# P-MT3620RDB-1-7_WiFi.net
KiCad netlist of a schematic drawn in Altium Designer
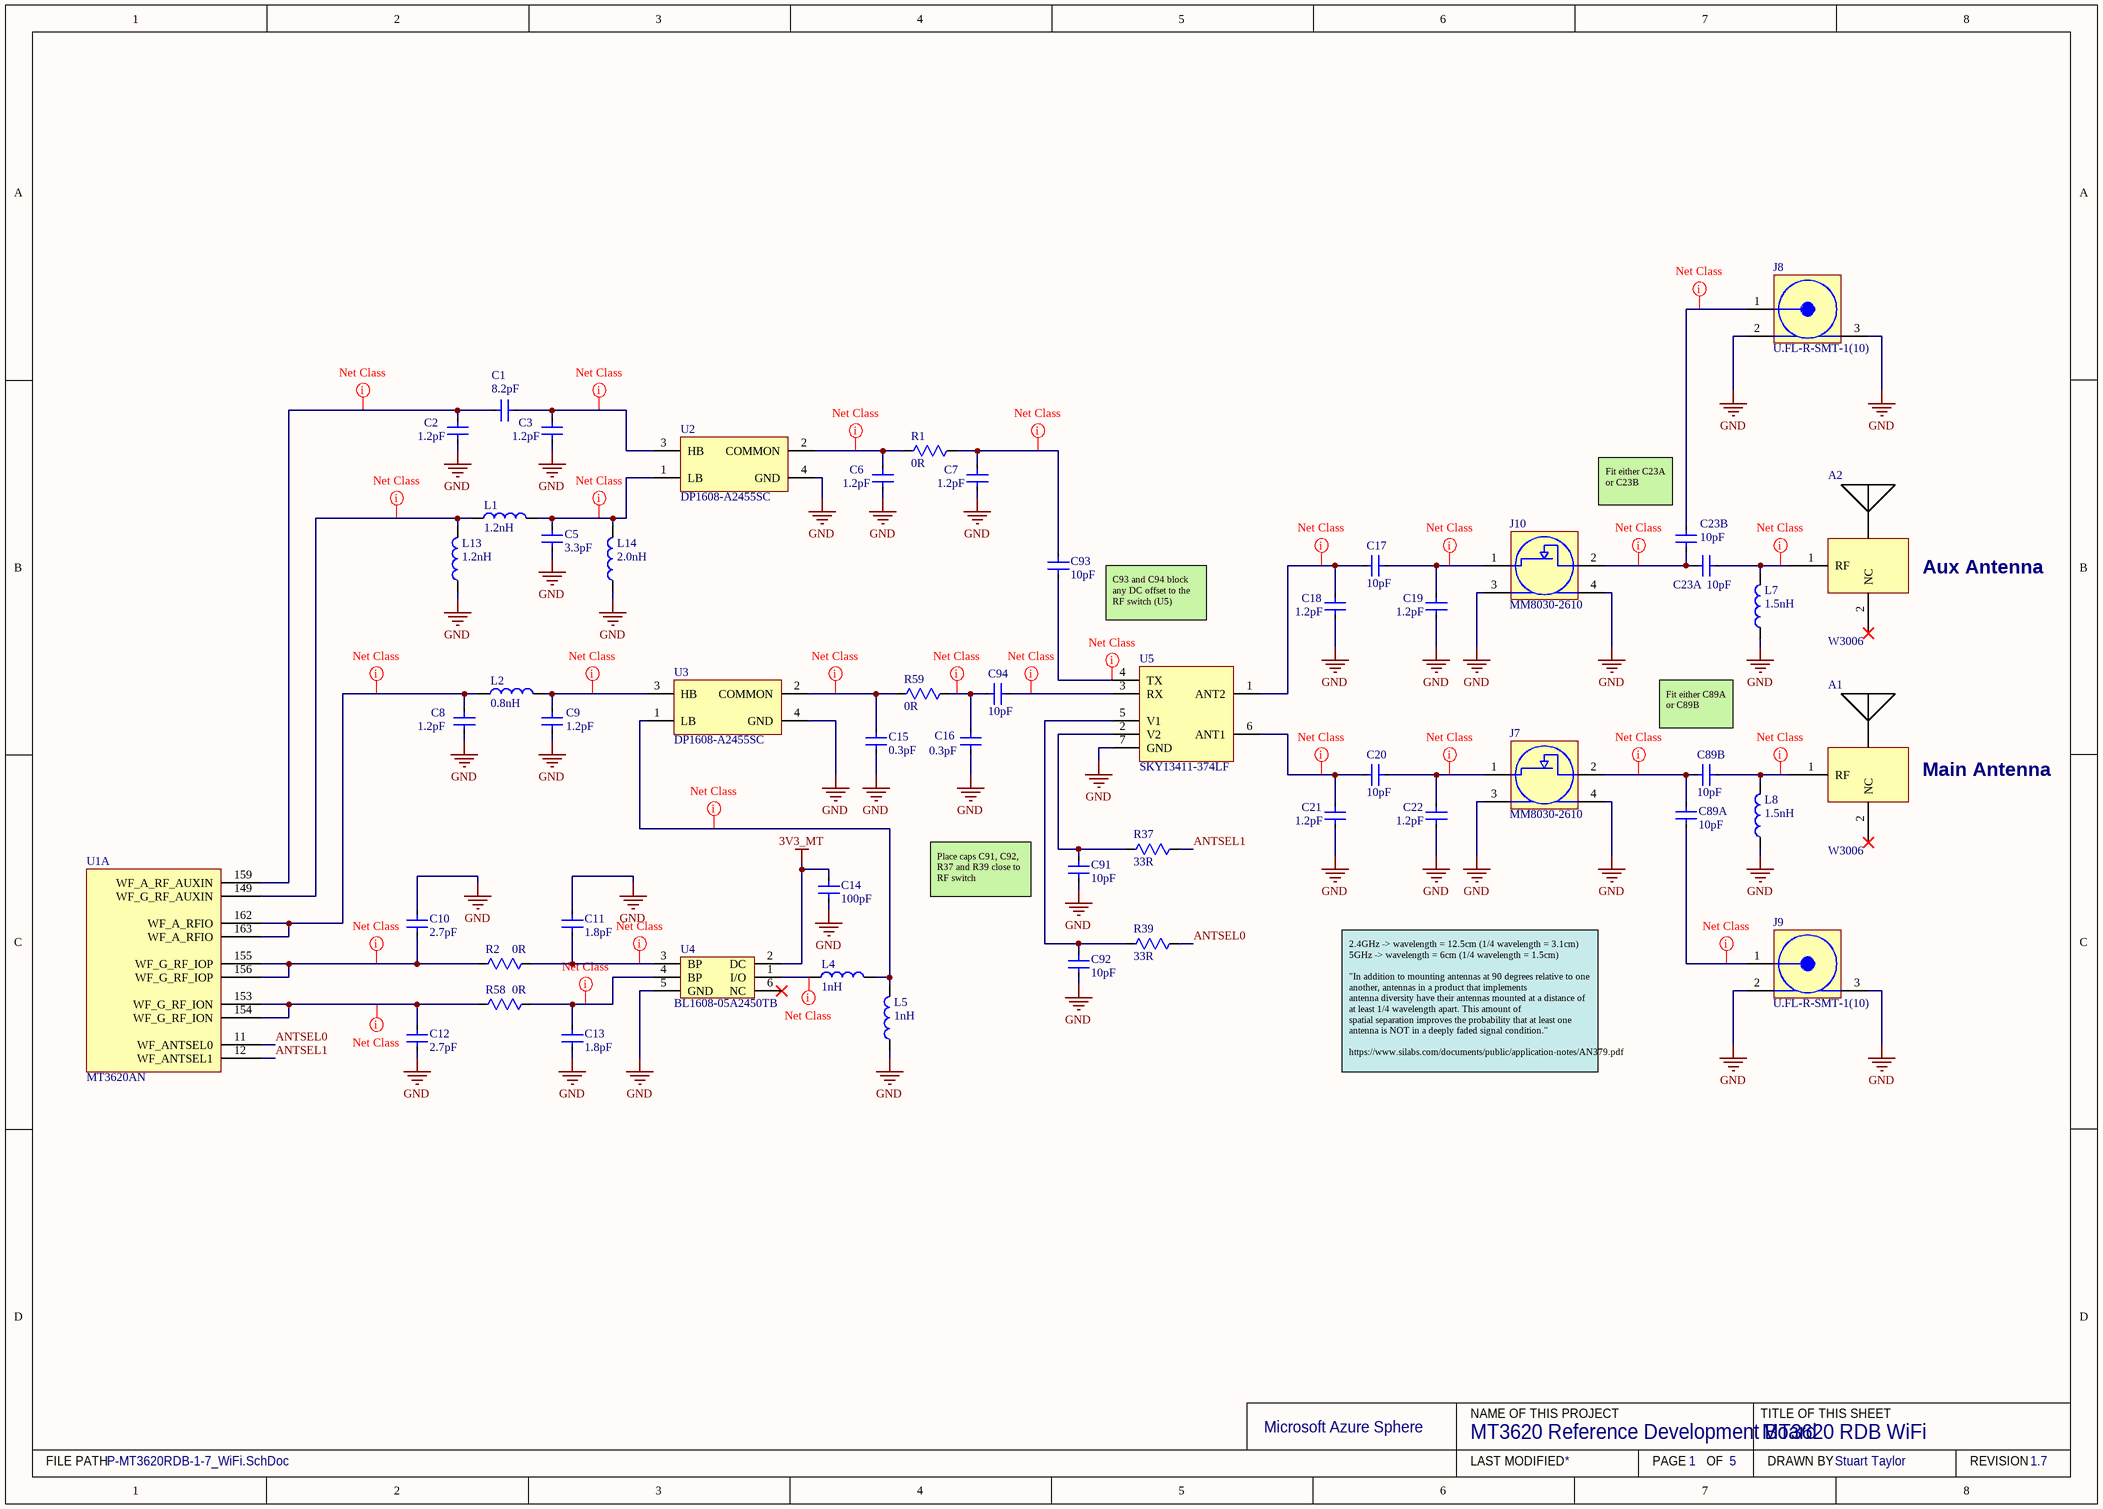
[diagram p0: P-MT3620RDB-1-7_WiFi.SchDoc]

(export (version "E")
  (design (tool "Eeschema 10.0.6"))
  (components
    (comp (ref "A1")
      (value "W3006")
      (footprint "W3006")
      (description "W3006 Chip Antenna")
      (fields (field (name "MANUFACTURER") "Pulse Electronics Corporation"))
      (libsource (lib "Pulse_W3006") (part "W3006"))
    )
    (comp (ref "A2")
      (value "W3006")
      (footprint "W3006")
      (description "W3006 Chip Antenna")
      (fields (field (name "MANUFACTURER") "Pulse Electronics Corporation"))
      (libsource (lib "Pulse_W3006") (part "W3006"))
    )
    (comp (ref "C1")
      (value "8.2pF")
      (footprint "TDK 2010")
      (description "CAP CER 8.2PF 25V NP0 0201")
      (fields
        (field (name "MANUFACTURER") "Murata")
        (field (name "MANUFACTURER PART NUMBER") "GJM0335C1E8R2CB01D")
      )
      (libsource (lib "Murata") (part "GJM0335C1E8R2CB01D"))
    )
    (comp (ref "C2")
      (value "1.2pF")
      (footprint "TDK 2010")
      (description "CAP CER 1.2PF 25V C0G 0201")
      (fields
        (field (name "MANUFACTURER") "TDK Corporation")
        (field (name "MANUFACTURER PART NUMBER") "C0603C0G1E1R2B")
      )
      (libsource (lib "TDK_Capacitor_C_0201") (part "1.2pF 0201 25V"))
    )
    (comp (ref "C3")
      (value "1.2pF")
      (footprint "TDK 2010")
      (description "CAP CER 1.2PF 25V C0G 0201")
      (fields
        (field (name "MANUFACTURER") "TDK Corporation")
        (field (name "MANUFACTURER PART NUMBER") "C0603C0G1E1R2B")
      )
      (libsource (lib "TDK_Capacitor_C_0201") (part "1.2pF 0201 25V"))
    )
    (comp (ref "C5")
      (value "3.3pF")
      (footprint "TDK 2010")
      (description "Cap Ceramic 3.3pF 25V C0G 0.25pF SMD 0201 125C T/R")
      (fields
        (field (name "MANUFACTURER") "TDK")
        (field (name "MANUFACTURER PART NUMBER") "CGA1A2C0G1E3R3C030BA")
      )
      (libsource (lib "TDK_Capacitor_C_0201") (part "3.3pF 0201 25V"))
    )
    (comp (ref "C6")
      (value "1.2pF")
      (footprint "TDK 2010")
      (description "CAP CER 1.2PF 25V C0G 0201")
      (fields
        (field (name "MANUFACTURER") "TDK Corporation")
        (field (name "MANUFACTURER PART NUMBER") "C0603C0G1E1R2B")
      )
      (libsource (lib "TDK_Capacitor_C_0201") (part "1.2pF 0201 25V"))
    )
    (comp (ref "C7")
      (value "1.2pF")
      (footprint "TDK 2010")
      (description "CAP CER 1.2PF 25V C0G 0201")
      (fields
        (field (name "MANUFACTURER") "TDK Corporation")
        (field (name "MANUFACTURER PART NUMBER") "C0603C0G1E1R2B")
      )
      (libsource (lib "TDK_Capacitor_C_0201") (part "1.2pF 0201 25V"))
    )
    (comp (ref "C8")
      (value "1.2pF")
      (footprint "TDK 2010")
      (description "CAP CER 1.2PF 25V C0G 0201")
      (fields
        (field (name "MANUFACTURER") "TDK Corporation")
        (field (name "MANUFACTURER PART NUMBER") "C0603C0G1E1R2B")
      )
      (libsource (lib "TDK_Capacitor_C_0201") (part "1.2pF 0201 25V"))
    )
    (comp (ref "C9")
      (value "1.2pF")
      (footprint "TDK 2010")
      (description "CAP CER 1.2PF 25V C0G 0201")
      (fields
        (field (name "MANUFACTURER") "TDK Corporation")
        (field (name "MANUFACTURER PART NUMBER") "C0603C0G1E1R2B")
      )
      (libsource (lib "TDK_Capacitor_C_0201") (part "1.2pF 0201 25V"))
    )
    (comp (ref "C10")
      (value "2.7pF")
      (footprint "TDK 2010")
      (description "CAP CER 2.7PF 25V C0G 0201")
      (fields (field (name "MANUFACTURER") "TDK") (field (name "MANUFACTURER PART NUMBER") "C0603C0G1E2R7B"))
      (libsource (lib "TDK_Capacitor_C_0201") (part "2.7pF 0201 25V"))
    )
    (comp (ref "C11")
      (value "1.8pF")
      (footprint "TDK 2010")
      (description "CAP CER 1.8PF 25V NP0 0201")
      (fields
        (field (name "MANUFACTURER") "Murata")
        (field (name "MANUFACTURER PART NUMBER") "GJM0335C1E1R8CB01D")
      )
      (libsource (lib "Murata") (part "GJM0335C1E1R8CB01D"))
    )
    (comp (ref "C12")
      (value "2.7pF")
      (footprint "TDK 2010")
      (description "CAP CER 2.7PF 25V C0G 0201")
      (fields (field (name "MANUFACTURER") "TDK") (field (name "MANUFACTURER PART NUMBER") "C0603C0G1E2R7B"))
      (libsource (lib "TDK_Capacitor_C_0201") (part "2.7pF 0201 25V"))
    )
    (comp (ref "C13")
      (value "1.8pF")
      (footprint "TDK 2010")
      (description "CAP CER 1.8PF 25V NP0 0201")
      (fields
        (field (name "MANUFACTURER") "Murata")
        (field (name "MANUFACTURER PART NUMBER") "GJM0335C1E1R8CB01D")
      )
      (libsource (lib "Murata") (part "GJM0335C1E1R8CB01D"))
    )
    (comp (ref "C14")
      (value "100pF")
      (footprint "CAPC1005-EIA0402 0.55MM MED")
      (description "CAP CER 100PF 50V 5% NP0 0402")
      (fields
        (field (name "MANUFACTURER") "TDK Corporation")
        (field (name "MANUFACTURER PART NUMBER") "C1005C0G1H101J050BA")
        (field (name "CAPACITANCE") "100pF")
      )
      (libsource (lib "TDK_Capacitor_C_0402") (part "100pF 0402 C0G, NP0 50V"))
    )
    (comp (ref "C15")
      (value "0.3pF")
      (footprint "TDK 2010")
      (description "CAP CER 0.3PF 25V C0G 0201")
      (fields
        (field (name "MANUFACTURER") "TDK Corporation")
        (field (name "MANUFACTURER PART NUMBER") "C0603C0G1E0R3B")
      )
      (libsource (lib "TDK_Capacitor_C_0201") (part "0.3pF 0201 25V"))
    )
    (comp (ref "C16")
      (value "0.3pF")
      (footprint "TDK 2010")
      (description "CAP CER 0.3PF 25V C0G 0201")
      (fields
        (field (name "MANUFACTURER") "TDK Corporation")
        (field (name "MANUFACTURER PART NUMBER") "C0603C0G1E0R3B")
      )
      (libsource (lib "TDK_Capacitor_C_0201") (part "0.3pF 0201 25V"))
    )
    (comp (ref "C17")
      (value "10pF")
      (footprint "TDK 2010")
      (description "CAP CER 10PF 25V C0G 0201")
      (fields
        (field (name "MANUFACTURER") "TDK Corporation")
        (field (name "MANUFACTURER PART NUMBER") "C0603C0G1E100D030BA")
      )
      (libsource (lib "TDK_Capacitor_C_0201") (part "10pF 0201 25V"))
    )
    (comp (ref "C18")
      (value "1.2pF")
      (footprint "TDK 2010")
      (description "CAP CER 1.2PF 25V C0G 0201")
      (fields
        (field (name "MANUFACTURER") "TDK Corporation")
        (field (name "MANUFACTURER PART NUMBER") "C0603C0G1E1R2B")
      )
      (libsource (lib "TDK_Capacitor_C_0201") (part "1.2pF 0201 25V"))
    )
    (comp (ref "C19")
      (value "1.2pF")
      (footprint "TDK 2010")
      (description "CAP CER 1.2PF 25V C0G 0201")
      (fields
        (field (name "MANUFACTURER") "TDK Corporation")
        (field (name "MANUFACTURER PART NUMBER") "C0603C0G1E1R2B")
      )
      (libsource (lib "TDK_Capacitor_C_0201") (part "1.2pF 0201 25V"))
    )
    (comp (ref "C20")
      (value "10pF")
      (footprint "TDK 2010")
      (description "CAP CER 10PF 25V C0G 0201")
      (fields
        (field (name "MANUFACTURER") "TDK Corporation")
        (field (name "MANUFACTURER PART NUMBER") "C0603C0G1E100D030BA")
      )
      (libsource (lib "TDK_Capacitor_C_0201") (part "10pF 0201 25V"))
    )
    (comp (ref "C21")
      (value "1.2pF")
      (footprint "TDK 2010")
      (description "CAP CER 1.2PF 25V C0G 0201")
      (fields
        (field (name "MANUFACTURER") "TDK Corporation")
        (field (name "MANUFACTURER PART NUMBER") "C0603C0G1E1R2B")
      )
      (libsource (lib "TDK_Capacitor_C_0201") (part "1.2pF 0201 25V"))
    )
    (comp (ref "C22")
      (value "1.2pF")
      (footprint "TDK 2010")
      (description "CAP CER 1.2PF 25V C0G 0201")
      (fields
        (field (name "MANUFACTURER") "TDK Corporation")
        (field (name "MANUFACTURER PART NUMBER") "C0603C0G1E1R2B")
      )
      (libsource (lib "TDK_Capacitor_C_0201") (part "1.2pF 0201 25V"))
    )
    (comp (ref "C23")
      (value "10pF")
      (footprint "CAPC1005-EIA0402 0.55MM MED - THREE WAY")
      (description "CAP CER 10PF 50V NP0 0402 - Three-way pads")
      (fields
        (field (name "MANUFACTURER") "TDK Corporation")
        (field (name "MANUFACTURER PART NUMBER") "C1005C0G1H100D050BA")
        (field (name "CAPACITANCE") "10pF")
      )
      (libsource (lib "TDK_Capacitor_C_0402") (part "10pF 0402 C0G, NP0 50V_1"))
    )
    (comp (ref "C89")
      (value "10pF")
      (footprint "CAPC1005-EIA0402 0.55MM MED - THREE WAY")
      (description "CAP CER 10PF 50V NP0 0402 - Three-way pads")
      (fields
        (field (name "MANUFACTURER") "TDK Corporation")
        (field (name "MANUFACTURER PART NUMBER") "C1005C0G1H100D050BA")
        (field (name "CAPACITANCE") "10pF")
      )
      (libsource (lib "TDK_Capacitor_C_0402") (part "10pF 0402 C0G, NP0 50V_1"))
    )
    (comp (ref "C91")
      (value "10pF")
      (footprint "TDK 2010")
      (description "CAP CER 10PF 25V C0G 0201")
      (fields
        (field (name "MANUFACTURER") "TDK Corporation")
        (field (name "MANUFACTURER PART NUMBER") "C0603C0G1E100D030BA")
      )
      (libsource (lib "TDK_Capacitor_C_0201") (part "10pF 0201 25V"))
    )
    (comp (ref "C92")
      (value "10pF")
      (footprint "TDK 2010")
      (description "CAP CER 10PF 25V C0G 0201")
      (fields
        (field (name "MANUFACTURER") "TDK Corporation")
        (field (name "MANUFACTURER PART NUMBER") "C0603C0G1E100D030BA")
      )
      (libsource (lib "TDK_Capacitor_C_0201") (part "10pF 0201 25V"))
    )
    (comp (ref "C93")
      (value "10pF")
      (footprint "TDK 2010")
      (description "CAP CER 10PF 25V C0G 0201")
      (fields
        (field (name "MANUFACTURER") "TDK Corporation")
        (field (name "MANUFACTURER PART NUMBER") "C0603C0G1E100D030BA")
      )
      (libsource (lib "TDK_Capacitor_C_0201") (part "10pF 0201 25V"))
    )
    (comp (ref "C94")
      (value "10pF")
      (footprint "TDK 2010")
      (description "CAP CER 10PF 25V C0G 0201")
      (fields
        (field (name "MANUFACTURER") "TDK Corporation")
        (field (name "MANUFACTURER PART NUMBER") "C0603C0G1E100D030BA")
      )
      (libsource (lib "TDK_Capacitor_C_0201") (part "10pF 0201 25V"))
    )
    (comp (ref "J7")
      (value "MM8030-2610")
      (footprint "MM8030-2610")
      (description "CONN UMC RECEPT SMD 2x2mm")
      (fields
        (field (name "MANUFACTURER") "Murata Electronics North America")
        (field (name "MANUFACTURER PART NUMBER") "MM8030-2610RK0")
      )
      (libsource (lib "Murata") (part "MM8030-2610"))
    )
    (comp (ref "J8")
      (value "U.FL-R-SMT-1(10)")
      (footprint "U.FL-R-SMT-1(10)")
      (description "CONN UMC JACK STR 50 OHM SMD")
      (fields (field (name "MANUFACTURER") "Hirose Electric (HRS)"))
      (libsource (lib "Hirose") (part "U.FL-R-SMT-1(10)"))
    )
    (comp (ref "J9")
      (value "U.FL-R-SMT-1(10)")
      (footprint "U.FL-R-SMT-1(10)")
      (description "CONN UMC JACK STR 50 OHM SMD")
      (fields (field (name "MANUFACTURER") "Hirose Electric (HRS)"))
      (libsource (lib "Hirose") (part "U.FL-R-SMT-1(10)"))
    )
    (comp (ref "J10")
      (value "MM8030-2610")
      (footprint "MM8030-2610")
      (description "CONN UMC RECEPT SMD 2x2mm")
      (fields
        (field (name "MANUFACTURER") "Murata Electronics North America")
        (field (name "MANUFACTURER PART NUMBER") "MM8030-2610RK0")
      )
      (libsource (lib "Murata") (part "MM8030-2610"))
    )
    (comp (ref "L1")
      (value "1.2nH")
      (footprint "TDK 2010")
      (description "FIXED IND 1.2NH 1A 80 MOHM SMD")
      (fields
        (field (name "MANUFACTURER") "TDK")
        (field (name "MANUFACTURER PART NUMBER") "MHQ0603P1N2CT000")
      )
      (libsource (lib "TDK") (part "1.2nH 0201"))
    )
    (comp (ref "L2")
      (value "0.8nH")
      (footprint "TDK 2010")
      (description "FIXED IND 0.8NH 1A 70 MOHM SMD")
      (fields
        (field (name "MANUFACTURER") "TDK Corporation")
        (field (name "MANUFACTURER PART NUMBER") "MHQ0603P0N8CT000")
      )
      (libsource (lib "TDK") (part "0.8nH 0201"))
    )
    (comp (ref "L4")
      (value "1nH")
      (footprint "TDK 2010")
      (description "FIXED IND 1NH 1A 70 MOHM SMD")
      (fields
        (field (name "MANUFACTURER") "TDK Corporation")
        (field (name "MANUFACTURER PART NUMBER") "MHQ0603P1N0CT000")
      )
      (libsource (lib "TDK") (part "1nH 0201"))
    )
    (comp (ref "L5")
      (value "1nH")
      (footprint "TDK 2010")
      (description "FIXED IND 1NH 1A 70 MOHM SMD")
      (fields
        (field (name "MANUFACTURER") "TDK Corporation")
        (field (name "MANUFACTURER PART NUMBER") "MHQ0603P1N0CT000")
      )
      (libsource (lib "TDK") (part "1nH 0201"))
    )
    (comp (ref "L7")
      (value "1.5nH")
      (footprint "TDK 2010")
      (description "MURATA - LQP03TN1N5B02D - INDUCTOR, 1.5NH, 0.6A, 0.1NH, 15GHZ")
      (fields
        (field (name "MANUFACTURER") "MURATA")
        (field (name "MANUFACTURER PART NUMBER") "LQP03TN1N5B02D")
      )
      (libsource (lib "Murata") (part "LQP03TN1N5B02D"))
    )
    (comp (ref "L8")
      (value "1.5nH")
      (footprint "TDK 2010")
      (description "MURATA - LQP03TN1N5B02D - INDUCTOR, 1.5NH, 0.6A, 0.1NH, 15GHZ")
      (fields
        (field (name "MANUFACTURER") "MURATA")
        (field (name "MANUFACTURER PART NUMBER") "LQP03TN1N5B02D")
      )
      (libsource (lib "Murata") (part "LQP03TN1N5B02D"))
    )
    (comp (ref "L13")
      (value "1.2nH")
      (footprint "TDK 2010")
      (description "FIXED IND 1.2NH 1A 80 MOHM SMD")
      (fields
        (field (name "MANUFACTURER") "TDK")
        (field (name "MANUFACTURER PART NUMBER") "MHQ0603P1N2CT000")
      )
      (libsource (lib "TDK") (part "1.2nH 0201"))
    )
    (comp (ref "L14")
      (value "2.0nH")
      (footprint "TDK 2010")
      (description "FIXED IND 2NH 700MA 120 MOHM SMD")
      (fields
        (field (name "MANUFACTURER") "TDK")
        (field (name "MANUFACTURER PART NUMBER") "MHQ0603P2N0CT000")
      )
      (libsource (lib "TDK") (part "2.0nH 0201"))
    )
    (comp (ref "R1")
      (value "0R")
      (footprint "TDK 2010")
      (description "RES SMD 0.0OHM JUMPER 1/20W 0201")
      (fields
        (field (name "MANUFACTURER") "Panasonic Electronic Components")
        (field (name "MANUFACTURER PART NUMBER") "ERJ-1GN0R00C")
      )
      (libsource (lib "Panasonic_Resistor_ERJ1GN") (part "0R 0201"))
    )
    (comp (ref "R2")
      (value "0R")
      (footprint "TDK 2010")
      (description "RES SMD 0.0OHM JUMPER 1/20W 0201")
      (fields
        (field (name "MANUFACTURER") "Panasonic Electronic Components")
        (field (name "MANUFACTURER PART NUMBER") "ERJ-1GN0R00C")
      )
      (libsource (lib "Panasonic_Resistor_ERJ1GN") (part "0R 0201"))
    )
    (comp (ref "R37")
      (value "33R")
      (footprint "RES 0402 MEDIUM DENSITY")
      (description "RES 33 OHM 1/10W 1% 0402 SMD")
      (fields
        (field (name "MANUFACTURER") "Panasonic Electronic Components")
        (field (name "MANUFACTURER PART NUMBER") "ERJ-2RKF33R0X")
        (field (name "RESISTANCE (OHMS)") "33R")
      )
      (libsource (lib "Panasonic_Resistor_ERJ2R") (part "33R"))
    )
    (comp (ref "R39")
      (value "33R")
      (footprint "RES 0402 MEDIUM DENSITY")
      (description "RES 33 OHM 1/10W 1% 0402 SMD")
      (fields
        (field (name "MANUFACTURER") "Panasonic Electronic Components")
        (field (name "MANUFACTURER PART NUMBER") "ERJ-2RKF33R0X")
        (field (name "RESISTANCE (OHMS)") "33R")
      )
      (libsource (lib "Panasonic_Resistor_ERJ2R") (part "33R"))
    )
    (comp (ref "R58")
      (value "0R")
      (footprint "TDK 2010")
      (description "RES SMD 0.0OHM JUMPER 1/20W 0201")
      (fields
        (field (name "MANUFACTURER") "Panasonic Electronic Components")
        (field (name "MANUFACTURER PART NUMBER") "ERJ-1GN0R00C")
      )
      (libsource (lib "Panasonic_Resistor_ERJ1GN") (part "0R 0201"))
    )
    (comp (ref "R59")
      (value "0R")
      (footprint "TDK 2010")
      (description "RES SMD 0.0OHM JUMPER 1/20W 0201")
      (fields
        (field (name "MANUFACTURER") "Panasonic Electronic Components")
        (field (name "MANUFACTURER PART NUMBER") "ERJ-1GN0R00C")
      )
      (libsource (lib "Panasonic_Resistor_ERJ1GN") (part "0R 0201"))
    )
    (comp (ref "U1")
      (value "MT3620AN")
      (footprint "Mt.Blanca")
      (libsource (lib "Microsoft") (part "MT3620AN"))
    )
    (comp (ref "U2")
      (value "DP1608-A2455SC")
      (footprint "DP1608-A2455SC")
      (description "Diplexer")
      (libsource (lib "ACX") (part "DP1608-A2455SC"))
    )
    (comp (ref "U3")
      (value "DP1608-A2455SC")
      (footprint "DP1608-A2455SC")
      (description "Diplexer")
      (libsource (lib "ACX") (part "DP1608-A2455SC"))
    )
    (comp (ref "U4")
      (value "BL1608-05A2450TB")
      (footprint "BL1608-05A2450TB")
      (description "Balun")
      (libsource (lib "ACX") (part "BL1608-05A2450TB"))
    )
    (comp (ref "U5")
      (value "SKY13411-374LF")
      (footprint "SKY13411-374LF")
      (description "RF SWITCH")
      (fields (field (name "MANUFACTURER") "Skyworks Solutions Inc."))
      (libsource (lib "Skyworks") (part "SKY13411-374LF"))
    )
  )
  (nets
    (net (code "1") (name "/ANTSEL0") (class "Default")
      (node (ref "R39") (pin "1") (pinfunction "1_1") (pintype "passive"))
      (node (ref "U1") (pin "11") (pinfunction "WF_ANTSEL0_11") (pintype "passive"))
    )
    (net (code "2") (name "/ANTSEL1") (class "Default")
      (node (ref "R37") (pin "1") (pinfunction "1_1") (pintype "passive"))
      (node (ref "U1") (pin "12") (pinfunction "WF_ANTSEL1_12") (pintype "passive"))
    )
    (net (code "3") (name "3V3_MT") (class "Default")
      (node (ref "C14") (pin "2") (pinfunction "2_2") (pintype "passive"))
      (node (ref "U4") (pin "2") (pinfunction "DC_2") (pintype "passive"))
    )
    (net (code "4") (name "GND") (class "Default")
      (node (ref "C10") (pin "2") (pinfunction "2_2") (pintype "passive"))
      (node (ref "C11") (pin "2") (pinfunction "2_2") (pintype "passive"))
      (node (ref "C12") (pin "1") (pinfunction "1_1") (pintype "passive"))
      (node (ref "C13") (pin "1") (pinfunction "1_1") (pintype "passive"))
      (node (ref "C14") (pin "1") (pinfunction "1_1") (pintype "passive"))
      (node (ref "C15") (pin "1") (pinfunction "1_1") (pintype "passive"))
      (node (ref "C16") (pin "1") (pinfunction "1_1") (pintype "passive"))
      (node (ref "C18") (pin "1") (pinfunction "1_1") (pintype "passive"))
      (node (ref "C19") (pin "1") (pinfunction "1_1") (pintype "passive"))
      (node (ref "C2") (pin "1") (pinfunction "1_1") (pintype "passive"))
      (node (ref "C21") (pin "1") (pinfunction "1_1") (pintype "passive"))
      (node (ref "C22") (pin "1") (pinfunction "1_1") (pintype "passive"))
      (node (ref "C3") (pin "1") (pinfunction "1_1") (pintype "passive"))
      (node (ref "C5") (pin "1") (pinfunction "1_1") (pintype "passive"))
      (node (ref "C6") (pin "1") (pinfunction "1_1") (pintype "passive"))
      (node (ref "C7") (pin "1") (pinfunction "1_1") (pintype "passive"))
      (node (ref "C8") (pin "1") (pinfunction "1_1") (pintype "passive"))
      (node (ref "C9") (pin "1") (pinfunction "1_1") (pintype "passive"))
      (node (ref "C91") (pin "1") (pinfunction "1_1") (pintype "passive"))
      (node (ref "C92") (pin "1") (pinfunction "1_1") (pintype "passive"))
      (node (ref "J10") (pin "3") (pinfunction "GND_3") (pintype "passive"))
      (node (ref "J10") (pin "4") (pinfunction "GND_4") (pintype "passive"))
      (node (ref "J7") (pin "3") (pinfunction "GND_3") (pintype "passive"))
      (node (ref "J7") (pin "4") (pinfunction "GND_4") (pintype "passive"))
      (node (ref "J8") (pin "2") (pinfunction "GND_2") (pintype "passive"))
      (node (ref "J8") (pin "3") (pinfunction "GND_3") (pintype "passive"))
      (node (ref "J9") (pin "2") (pinfunction "GND_2") (pintype "passive"))
      (node (ref "J9") (pin "3") (pinfunction "GND_3") (pintype "passive"))
      (node (ref "L13") (pin "1") (pinfunction "1_1") (pintype "passive"))
      (node (ref "L14") (pin "1") (pinfunction "1_1") (pintype "passive"))
      (node (ref "L5") (pin "1") (pinfunction "1_1") (pintype "passive"))
      (node (ref "L7") (pin "1") (pinfunction "1_1") (pintype "passive"))
      (node (ref "L8") (pin "1") (pinfunction "1_1") (pintype "passive"))
      (node (ref "U2") (pin "4") (pinfunction "GND_4") (pintype "passive"))
      (node (ref "U3") (pin "4") (pinfunction "GND_4") (pintype "passive"))
      (node (ref "U4") (pin "5") (pinfunction "GND_5") (pintype "passive"))
      (node (ref "U5") (pin "7") (pinfunction "GND_7") (pintype "passive"))
    )
    (net (code "5") (name "Net-(A1-RF)") (class "Default")
      (node (ref "A1") (pin "1") (pinfunction "RF_1") (pintype "passive"))
      (node (ref "C89") (pin "3") (pinfunction "3_3") (pintype "passive"))
      (node (ref "L8") (pin "2") (pinfunction "2_2") (pintype "passive"))
    )
    (net (code "6") (name "Net-(A2-RF)") (class "Default")
      (node (ref "A2") (pin "1") (pinfunction "RF_1") (pintype "passive"))
      (node (ref "C23") (pin "2") (pinfunction "2_2") (pintype "passive"))
      (node (ref "L7") (pin "2") (pinfunction "2_2") (pintype "passive"))
    )
    (net (code "7") (name "Net-(C7-Pad2)") (class "Default")
      (node (ref "C7") (pin "2") (pinfunction "2_2") (pintype "passive"))
      (node (ref "C93") (pin "2") (pinfunction "2_2") (pintype "passive"))
      (node (ref "R1") (pin "1") (pinfunction "1_1") (pintype "passive"))
    )
    (net (code "8") (name "Net-(C8-Pad2)") (class "Default")
      (node (ref "C8") (pin "2") (pinfunction "2_2") (pintype "passive"))
      (node (ref "L2") (pin "1") (pinfunction "1_1") (pintype "passive"))
      (node (ref "U1") (pin "162") (pinfunction "WF_A_RFIO_162") (pintype "passive"))
      (node (ref "U1") (pin "163") (pinfunction "WF_A_RFIO_163") (pintype "passive"))
    )
    (net (code "9") (name "Net-(C10-Pad1)") (class "Default")
      (node (ref "C10") (pin "1") (pinfunction "1_1") (pintype "passive"))
      (node (ref "R2") (pin "2") (pinfunction "2_2") (pintype "passive"))
      (node (ref "U1") (pin "155") (pinfunction "WF_G_RF_IOP_155") (pintype "passive"))
      (node (ref "U1") (pin "156") (pinfunction "WF_G_RF_IOP_156") (pintype "passive"))
    )
    (net (code "10") (name "Net-(C11-Pad1)") (class "Default")
      (node (ref "C11") (pin "1") (pinfunction "1_1") (pintype "passive"))
      (node (ref "R2") (pin "1") (pinfunction "1_1") (pintype "passive"))
      (node (ref "U4") (pin "3") (pinfunction "BP_3") (pintype "passive"))
    )
    (net (code "11") (name "Net-(C12-Pad2)") (class "Default")
      (node (ref "C12") (pin "2") (pinfunction "2_2") (pintype "passive"))
      (node (ref "R58") (pin "2") (pinfunction "2_2") (pintype "passive"))
      (node (ref "U1") (pin "153") (pinfunction "WF_G_RF_ION_153") (pintype "passive"))
      (node (ref "U1") (pin "154") (pinfunction "WF_G_RF_ION_154") (pintype "passive"))
    )
    (net (code "12") (name "Net-(C13-Pad2)") (class "Default")
      (node (ref "C13") (pin "2") (pinfunction "2_2") (pintype "passive"))
      (node (ref "R58") (pin "1") (pinfunction "1_1") (pintype "passive"))
      (node (ref "U4") (pin "4") (pinfunction "BP_4") (pintype "passive"))
    )
    (net (code "13") (name "Net-(C16-Pad2)") (class "Default")
      (node (ref "C16") (pin "2") (pinfunction "2_2") (pintype "passive"))
      (node (ref "C94") (pin "2") (pinfunction "2_2") (pintype "passive"))
      (node (ref "R59") (pin "1") (pinfunction "1_1") (pintype "passive"))
    )
    (net (code "14") (name "Net-(J7-IN)") (class "Default")
      (node (ref "C20") (pin "2") (pinfunction "2_2") (pintype "passive"))
      (node (ref "C22") (pin "2") (pinfunction "2_2") (pintype "passive"))
      (node (ref "J7") (pin "1") (pinfunction "IN_1") (pintype "passive"))
    )
    (net (code "15") (name "Net-(J7-OUT)") (class "Default")
      (node (ref "C89") (pin "1") (pinfunction "1_1") (pintype "passive"))
      (node (ref "J7") (pin "2") (pinfunction "OUT_2") (pintype "passive"))
    )
    (net (code "16") (name "Net-(J8-IN)") (class "Default")
      (node (ref "C23") (pin "3") (pinfunction "3_3") (pintype "passive"))
      (node (ref "J8") (pin "1") (pinfunction "IN_1") (pintype "passive"))
    )
    (net (code "17") (name "Net-(J9-IN)") (class "Default")
      (node (ref "C89") (pin "2") (pinfunction "2_2") (pintype "passive"))
      (node (ref "J9") (pin "1") (pinfunction "IN_1") (pintype "passive"))
    )
    (net (code "18") (name "Net-(J10-IN)") (class "Default")
      (node (ref "C17") (pin "2") (pinfunction "2_2") (pintype "passive"))
      (node (ref "C19") (pin "2") (pinfunction "2_2") (pintype "passive"))
      (node (ref "J10") (pin "1") (pinfunction "IN_1") (pintype "passive"))
    )
    (net (code "19") (name "Net-(J10-OUT)") (class "Default")
      (node (ref "C23") (pin "1") (pinfunction "1_1") (pintype "passive"))
      (node (ref "J10") (pin "2") (pinfunction "OUT_2") (pintype "passive"))
    )
    (net (code "20") (name "Net-(U1A-WF_A_RF_AUXIN)") (class "Default")
      (node (ref "C1") (pin "1") (pinfunction "1_1") (pintype "passive"))
      (node (ref "C2") (pin "2") (pinfunction "2_2") (pintype "passive"))
      (node (ref "U1") (pin "159") (pinfunction "WF_A_RF_AUXIN_159") (pintype "passive"))
    )
    (net (code "21") (name "Net-(U1A-WF_G_RF_AUXIN)") (class "Default")
      (node (ref "L1") (pin "1") (pinfunction "1_1") (pintype "passive"))
      (node (ref "L13") (pin "2") (pinfunction "2_2") (pintype "passive"))
      (node (ref "U1") (pin "149") (pinfunction "WF_G_RF_AUXIN_149") (pintype "passive"))
    )
    (net (code "22") (name "Net-(U2-COMMON)") (class "Default")
      (node (ref "C6") (pin "2") (pinfunction "2_2") (pintype "passive"))
      (node (ref "R1") (pin "2") (pinfunction "2_2") (pintype "passive"))
      (node (ref "U2") (pin "2") (pinfunction "COMMON_2") (pintype "passive"))
    )
    (net (code "23") (name "Net-(U2-HB)") (class "Default")
      (node (ref "C1") (pin "2") (pinfunction "2_2") (pintype "passive"))
      (node (ref "C3") (pin "2") (pinfunction "2_2") (pintype "passive"))
      (node (ref "U2") (pin "3") (pinfunction "HB_3") (pintype "passive"))
    )
    (net (code "24") (name "Net-(U2-LB)") (class "Default")
      (node (ref "C5") (pin "2") (pinfunction "2_2") (pintype "passive"))
      (node (ref "L1") (pin "2") (pinfunction "2_2") (pintype "passive"))
      (node (ref "L14") (pin "2") (pinfunction "2_2") (pintype "passive"))
      (node (ref "U2") (pin "1") (pinfunction "LB_1") (pintype "passive"))
    )
    (net (code "25") (name "Net-(U3-COMMON)") (class "Default")
      (node (ref "C15") (pin "2") (pinfunction "2_2") (pintype "passive"))
      (node (ref "R59") (pin "2") (pinfunction "2_2") (pintype "passive"))
      (node (ref "U3") (pin "2") (pinfunction "COMMON_2") (pintype "passive"))
    )
    (net (code "26") (name "Net-(U3-HB)") (class "Default")
      (node (ref "C9") (pin "2") (pinfunction "2_2") (pintype "passive"))
      (node (ref "L2") (pin "2") (pinfunction "2_2") (pintype "passive"))
      (node (ref "U3") (pin "3") (pinfunction "HB_3") (pintype "passive"))
    )
    (net (code "27") (name "Net-(U3-LB)") (class "Default")
      (node (ref "L4") (pin "2") (pinfunction "2_2") (pintype "passive"))
      (node (ref "L5") (pin "2") (pinfunction "2_2") (pintype "passive"))
      (node (ref "U3") (pin "1") (pinfunction "LB_1") (pintype "passive"))
    )
    (net (code "28") (name "Net-(U4-I{slash}O)") (class "Default")
      (node (ref "L4") (pin "1") (pinfunction "1_1") (pintype "passive"))
      (node (ref "U4") (pin "1") (pinfunction "I/O_1") (pintype "passive"))
    )
    (net (code "29") (name "Net-(U5-ANT1)") (class "Default")
      (node (ref "C20") (pin "1") (pinfunction "1_1") (pintype "passive"))
      (node (ref "C21") (pin "2") (pinfunction "2_2") (pintype "passive"))
      (node (ref "U5") (pin "6") (pinfunction "ANT1_6") (pintype "passive"))
    )
    (net (code "30") (name "Net-(U5-ANT2)") (class "Default")
      (node (ref "C17") (pin "1") (pinfunction "1_1") (pintype "passive"))
      (node (ref "C18") (pin "2") (pinfunction "2_2") (pintype "passive"))
      (node (ref "U5") (pin "1") (pinfunction "ANT2_1") (pintype "passive"))
    )
    (net (code "31") (name "Net-(U5-RX)") (class "Default")
      (node (ref "C94") (pin "1") (pinfunction "1_1") (pintype "passive"))
      (node (ref "U5") (pin "3") (pinfunction "RX_3") (pintype "passive"))
    )
    (net (code "32") (name "Net-(U5-TX)") (class "Default")
      (node (ref "C93") (pin "1") (pinfunction "1_1") (pintype "passive"))
      (node (ref "U5") (pin "4") (pinfunction "TX_4") (pintype "passive"))
    )
    (net (code "33") (name "Net-(U5-V1)") (class "Default")
      (node (ref "C92") (pin "2") (pinfunction "2_2") (pintype "passive"))
      (node (ref "R39") (pin "2") (pinfunction "2_2") (pintype "passive"))
      (node (ref "U5") (pin "5") (pinfunction "V1_5") (pintype "passive"))
    )
    (net (code "34") (name "Net-(U5-V2)") (class "Default")
      (node (ref "C91") (pin "2") (pinfunction "2_2") (pintype "passive"))
      (node (ref "R37") (pin "2") (pinfunction "2_2") (pintype "passive"))
      (node (ref "U5") (pin "2") (pinfunction "V2_2") (pintype "passive"))
    )
    (net (code "35") (name "unconnected-(A1-NC-Pad2)") (class "Default")
      (node (ref "A1") (pin "2") (pinfunction "NC_2") (pintype "passive+no_connect"))
    )
    (net (code "36") (name "unconnected-(A2-NC-Pad2)") (class "Default")
      (node (ref "A2") (pin "2") (pinfunction "NC_2") (pintype "passive+no_connect"))
    )
    (net (code "37") (name "unconnected-(U4-NC-Pad6)") (class "Default")
      (node (ref "U4") (pin "6") (pinfunction "NC_6") (pintype "passive+no_connect"))
    )
  )
)
